# PWM_WIDTH.net
KiCad netlist of a schematic drawn in Altium Designer
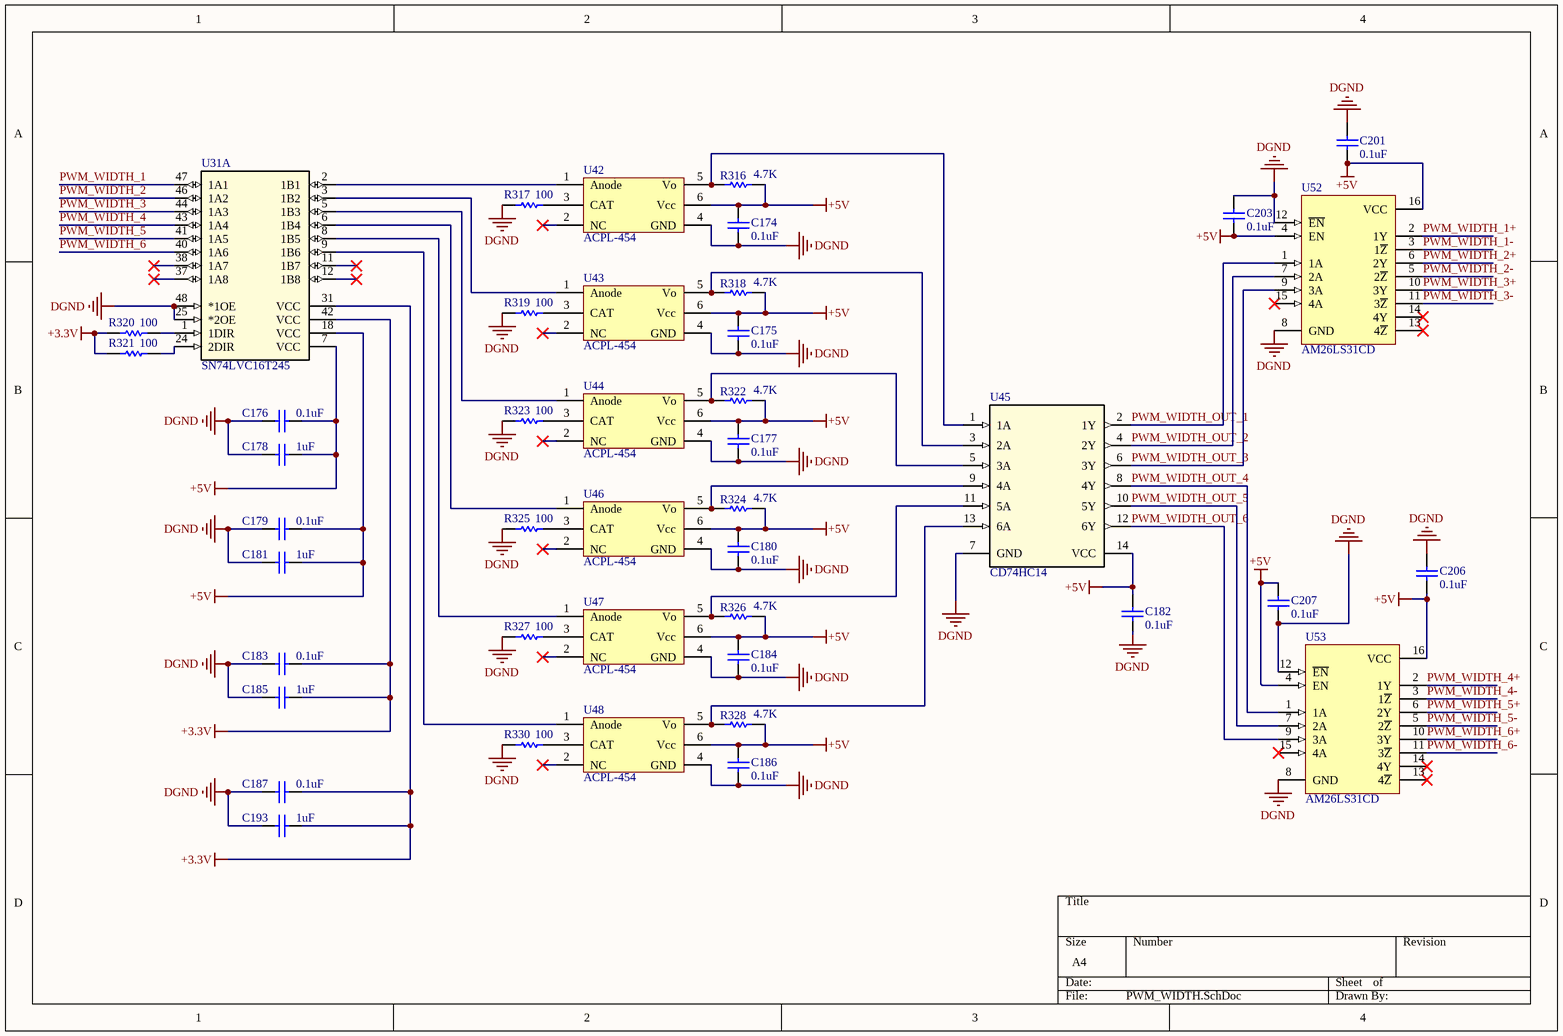
[diagram p0: PWM_WIDTH.SchDoc]

(export (version "E")
  (design (tool "Eeschema 10.0.6"))
  (components
    (comp (ref "C174")
      (value "0.1uF")
      (footprint "1608[0603]")
      (description "Capacitor")
      (fields (field (name "Comment") "Cap") (field (name "PUBLISHER") "Altium Limited"))
      (libsource (lib "Miscellaneous Devices") (part "Cap"))
    )
    (comp (ref "C175")
      (value "0.1uF")
      (footprint "1608[0603]")
      (description "Capacitor")
      (fields (field (name "Comment") "Cap") (field (name "PUBLISHER") "Altium Limited"))
      (libsource (lib "Miscellaneous Devices") (part "Cap"))
    )
    (comp (ref "C176")
      (value "0.1uF")
      (footprint "1608[0603]")
      (description "Capacitor")
      (fields (field (name "Comment") "Cap") (field (name "PUBLISHER") "Altium Limited"))
      (libsource (lib "Miscellaneous Devices") (part "Cap"))
    )
    (comp (ref "C177")
      (value "0.1uF")
      (footprint "1608[0603]")
      (description "Capacitor")
      (fields (field (name "Comment") "Cap") (field (name "PUBLISHER") "Altium Limited"))
      (libsource (lib "Miscellaneous Devices") (part "Cap"))
    )
    (comp (ref "C178")
      (value "1uF")
      (footprint "1608[0603]")
      (description "Capacitor")
      (fields (field (name "Comment") "Cap") (field (name "PUBLISHER") "Altium Limited"))
      (libsource (lib "Miscellaneous Devices") (part "Cap"))
    )
    (comp (ref "C179")
      (value "0.1uF")
      (footprint "1608[0603]")
      (description "Capacitor")
      (fields (field (name "Comment") "Cap") (field (name "PUBLISHER") "Altium Limited"))
      (libsource (lib "Miscellaneous Devices") (part "Cap"))
    )
    (comp (ref "C180")
      (value "0.1uF")
      (footprint "1608[0603]")
      (description "Capacitor")
      (fields (field (name "Comment") "Cap") (field (name "PUBLISHER") "Altium Limited"))
      (libsource (lib "Miscellaneous Devices") (part "Cap"))
    )
    (comp (ref "C181")
      (value "1uF")
      (footprint "1608[0603]")
      (description "Capacitor")
      (fields (field (name "Comment") "Cap") (field (name "PUBLISHER") "Altium Limited"))
      (libsource (lib "Miscellaneous Devices") (part "Cap"))
    )
    (comp (ref "C182")
      (value "0.1uF")
      (footprint "1608[0603]")
      (description "Capacitor")
      (fields (field (name "Comment") "Cap") (field (name "PUBLISHER") "Altium Limited"))
      (libsource (lib "Miscellaneous Devices") (part "Cap"))
    )
    (comp (ref "C183")
      (value "0.1uF")
      (footprint "1608[0603]")
      (description "Capacitor")
      (fields (field (name "Comment") "Cap") (field (name "PUBLISHER") "Altium Limited"))
      (libsource (lib "Miscellaneous Devices") (part "Cap"))
    )
    (comp (ref "C184")
      (value "0.1uF")
      (footprint "1608[0603]")
      (description "Capacitor")
      (fields (field (name "Comment") "Cap") (field (name "PUBLISHER") "Altium Limited"))
      (libsource (lib "Miscellaneous Devices") (part "Cap"))
    )
    (comp (ref "C185")
      (value "1uF")
      (footprint "1608[0603]")
      (description "Capacitor")
      (fields (field (name "Comment") "Cap") (field (name "PUBLISHER") "Altium Limited"))
      (libsource (lib "Miscellaneous Devices") (part "Cap"))
    )
    (comp (ref "C186")
      (value "0.1uF")
      (footprint "1608[0603]")
      (description "Capacitor")
      (fields (field (name "Comment") "Cap") (field (name "PUBLISHER") "Altium Limited"))
      (libsource (lib "Miscellaneous Devices") (part "Cap"))
    )
    (comp (ref "C187")
      (value "0.1uF")
      (footprint "1608[0603]")
      (description "Capacitor")
      (fields (field (name "Comment") "Cap") (field (name "PUBLISHER") "Altium Limited"))
      (libsource (lib "Miscellaneous Devices") (part "Cap"))
    )
    (comp (ref "C193")
      (value "1uF")
      (footprint "1608[0603]")
      (description "Capacitor")
      (fields (field (name "Comment") "Cap") (field (name "PUBLISHER") "Altium Limited"))
      (libsource (lib "Miscellaneous Devices") (part "Cap"))
    )
    (comp (ref "C201")
      (value "0.1uF")
      (footprint "1608[0603]")
      (description "Capacitor")
      (fields (field (name "Comment") "Cap") (field (name "PUBLISHER") "Altium Limited"))
      (libsource (lib "Miscellaneous Devices") (part "Cap"))
    )
    (comp (ref "C203")
      (value "0.1uF")
      (footprint "1608[0603]")
      (description "Capacitor")
      (fields (field (name "Comment") "Cap") (field (name "PUBLISHER") "Altium Limited"))
      (libsource (lib "Miscellaneous Devices") (part "Cap"))
    )
    (comp (ref "C206")
      (value "0.1uF")
      (footprint "1608[0603]")
      (description "Capacitor")
      (fields (field (name "Comment") "Cap") (field (name "PUBLISHER") "Altium Limited"))
      (libsource (lib "Miscellaneous Devices") (part "Cap"))
    )
    (comp (ref "C207")
      (value "0.1uF")
      (footprint "1608[0603]")
      (description "Capacitor")
      (fields (field (name "Comment") "Cap") (field (name "PUBLISHER") "Altium Limited"))
      (libsource (lib "Miscellaneous Devices") (part "Cap"))
    )
    (comp (ref "R316")
      (value "4.7K")
      (footprint "1608[0603]")
      (description "Resistor")
      (fields (field (name "Comment") "Res1") (field (name "PUBLISHER") "Altium Limited"))
      (libsource (lib "Miscellaneous Devices") (part "Res1"))
    )
    (comp (ref "R317")
      (value "100")
      (footprint "1608[0603]")
      (description "Resistor")
      (fields (field (name "Comment") "Res1") (field (name "PUBLISHER") "Altium Limited"))
      (libsource (lib "Miscellaneous Devices") (part "Res1"))
    )
    (comp (ref "R318")
      (value "4.7K")
      (footprint "1608[0603]")
      (description "Resistor")
      (fields (field (name "Comment") "Res1") (field (name "PUBLISHER") "Altium Limited"))
      (libsource (lib "Miscellaneous Devices") (part "Res1"))
    )
    (comp (ref "R319")
      (value "100")
      (footprint "1608[0603]")
      (description "Resistor")
      (fields (field (name "Comment") "Res1") (field (name "PUBLISHER") "Altium Limited"))
      (libsource (lib "Miscellaneous Devices") (part "Res1"))
    )
    (comp (ref "R320")
      (value "100")
      (footprint "1608[0603]")
      (description "Resistor")
      (fields (field (name "Comment") "Res1") (field (name "PUBLISHER") "Altium Limited"))
      (libsource (lib "Miscellaneous Devices") (part "Res1"))
    )
    (comp (ref "R321")
      (value "100")
      (footprint "1608[0603]")
      (description "Resistor")
      (fields (field (name "Comment") "Res1") (field (name "PUBLISHER") "Altium Limited"))
      (libsource (lib "Miscellaneous Devices") (part "Res1"))
    )
    (comp (ref "R322")
      (value "4.7K")
      (footprint "1608[0603]")
      (description "Resistor")
      (fields (field (name "Comment") "Res1") (field (name "PUBLISHER") "Altium Limited"))
      (libsource (lib "Miscellaneous Devices") (part "Res1"))
    )
    (comp (ref "R323")
      (value "100")
      (footprint "1608[0603]")
      (description "Resistor")
      (fields (field (name "Comment") "Res1") (field (name "PUBLISHER") "Altium Limited"))
      (libsource (lib "Miscellaneous Devices") (part "Res1"))
    )
    (comp (ref "R324")
      (value "4.7K")
      (footprint "1608[0603]")
      (description "Resistor")
      (fields (field (name "Comment") "Res1") (field (name "PUBLISHER") "Altium Limited"))
      (libsource (lib "Miscellaneous Devices") (part "Res1"))
    )
    (comp (ref "R325")
      (value "100")
      (footprint "1608[0603]")
      (description "Resistor")
      (fields (field (name "Comment") "Res1") (field (name "PUBLISHER") "Altium Limited"))
      (libsource (lib "Miscellaneous Devices") (part "Res1"))
    )
    (comp (ref "R326")
      (value "4.7K")
      (footprint "1608[0603]")
      (description "Resistor")
      (fields (field (name "Comment") "Res1") (field (name "PUBLISHER") "Altium Limited"))
      (libsource (lib "Miscellaneous Devices") (part "Res1"))
    )
    (comp (ref "R327")
      (value "100")
      (footprint "1608[0603]")
      (description "Resistor")
      (fields (field (name "Comment") "Res1") (field (name "PUBLISHER") "Altium Limited"))
      (libsource (lib "Miscellaneous Devices") (part "Res1"))
    )
    (comp (ref "R328")
      (value "4.7K")
      (footprint "1608[0603]")
      (description "Resistor")
      (fields (field (name "Comment") "Res1") (field (name "PUBLISHER") "Altium Limited"))
      (libsource (lib "Miscellaneous Devices") (part "Res1"))
    )
    (comp (ref "R330")
      (value "100")
      (footprint "1608[0603]")
      (description "Resistor")
      (fields (field (name "Comment") "Res1") (field (name "PUBLISHER") "Altium Limited"))
      (libsource (lib "Miscellaneous Devices") (part "Res1"))
    )
    (comp (ref "U31")
      (value "SN74LVC16T245")
      (footprint "SN74LVC16T245_TSSOP")
      (libsource (lib "DSP_FPGA_Lib") (part "SN74LVC16T245_A"))
    )
    (comp (ref "U42")
      (value "ACPL-454")
      (footprint "ACPL-P454")
      (libsource (lib "DSP_FPGA_Lib") (part "ACPL-454"))
    )
    (comp (ref "U43")
      (value "ACPL-454")
      (footprint "ACPL-P454")
      (libsource (lib "DSP_FPGA_Lib") (part "ACPL-454"))
    )
    (comp (ref "U44")
      (value "ACPL-454")
      (footprint "ACPL-P454")
      (libsource (lib "DSP_FPGA_Lib") (part "ACPL-454"))
    )
    (comp (ref "U45")
      (value "CD74HC14")
      (footprint "CD74HC14_SOIC")
      (fields (field (name "MANUFACTURER") "Texas Instruments"))
      (libsource (lib "DSP_FPGA_Lib") (part "CD74HC14"))
    )
    (comp (ref "U46")
      (value "ACPL-454")
      (footprint "ACPL-P454")
      (libsource (lib "DSP_FPGA_Lib") (part "ACPL-454"))
    )
    (comp (ref "U47")
      (value "ACPL-454")
      (footprint "ACPL-P454")
      (libsource (lib "DSP_FPGA_Lib") (part "ACPL-454"))
    )
    (comp (ref "U48")
      (value "ACPL-454")
      (footprint "ACPL-P454")
      (libsource (lib "DSP_FPGA_Lib") (part "ACPL-454"))
    )
    (comp (ref "U52")
      (value "AM26LS31CD")
      (footprint "D016_N")
      (description "Quadruple Differential Line Driver")
      (fields (field (name "PUBLISHER") "Altium Limited"))
      (libsource (lib "TI Interface Line Driver") (part "AM26LS31CD"))
    )
    (comp (ref "U53")
      (value "AM26LS31CD")
      (footprint "D016_N")
      (description "Quadruple Differential Line Driver")
      (fields (field (name "PUBLISHER") "Altium Limited"))
      (libsource (lib "TI Interface Line Driver") (part "AM26LS31CD"))
    )
  )
  (nets
    (net (code "1") (name "+3.3V") (class "Default")
      (node (ref "C183") (pin "1") (pinfunction "1_1") (pintype "passive"))
      (node (ref "C185") (pin "1") (pinfunction "1_1") (pintype "passive"))
      (node (ref "C187") (pin "1") (pinfunction "1_1") (pintype "passive"))
      (node (ref "C193") (pin "1") (pinfunction "1_1") (pintype "passive"))
      (node (ref "R320") (pin "2") (pinfunction "2_2") (pintype "passive"))
      (node (ref "R321") (pin "2") (pinfunction "2_2") (pintype "passive"))
      (node (ref "U31") (pin "31") (pinfunction "VCC_31") (pintype "power_in"))
      (node (ref "U31") (pin "42") (pinfunction "VCC_42") (pintype "power_in"))
    )
    (net (code "2") (name "+5V") (class "Default")
      (node (ref "C174") (pin "2") (pinfunction "2_2") (pintype "passive"))
      (node (ref "C175") (pin "2") (pinfunction "2_2") (pintype "passive"))
      (node (ref "C176") (pin "1") (pinfunction "1_1") (pintype "passive"))
      (node (ref "C177") (pin "2") (pinfunction "2_2") (pintype "passive"))
      (node (ref "C178") (pin "1") (pinfunction "1_1") (pintype "passive"))
      (node (ref "C179") (pin "1") (pinfunction "1_1") (pintype "passive"))
      (node (ref "C180") (pin "2") (pinfunction "2_2") (pintype "passive"))
      (node (ref "C181") (pin "1") (pinfunction "1_1") (pintype "passive"))
      (node (ref "C182") (pin "2") (pinfunction "2_2") (pintype "passive"))
      (node (ref "C184") (pin "2") (pinfunction "2_2") (pintype "passive"))
      (node (ref "C186") (pin "2") (pinfunction "2_2") (pintype "passive"))
      (node (ref "C201") (pin "2") (pinfunction "2_2") (pintype "passive"))
      (node (ref "C203") (pin "1") (pinfunction "1_1") (pintype "passive"))
      (node (ref "C206") (pin "1") (pinfunction "1_1") (pintype "passive"))
      (node (ref "C207") (pin "2") (pinfunction "2_2") (pintype "passive"))
      (node (ref "R316") (pin "1") (pinfunction "1_1") (pintype "passive"))
      (node (ref "R318") (pin "1") (pinfunction "1_1") (pintype "passive"))
      (node (ref "R322") (pin "1") (pinfunction "1_1") (pintype "passive"))
      (node (ref "R324") (pin "1") (pinfunction "1_1") (pintype "passive"))
      (node (ref "R326") (pin "1") (pinfunction "1_1") (pintype "passive"))
      (node (ref "R328") (pin "1") (pinfunction "1_1") (pintype "passive"))
      (node (ref "U31") (pin "18") (pinfunction "VCC_18") (pintype "power_in"))
      (node (ref "U31") (pin "7") (pinfunction "VCC_7") (pintype "power_in"))
      (node (ref "U42") (pin "6") (pinfunction "Vcc_6") (pintype "passive"))
      (node (ref "U43") (pin "6") (pinfunction "Vcc_6") (pintype "passive"))
      (node (ref "U44") (pin "6") (pinfunction "Vcc_6") (pintype "passive"))
      (node (ref "U45") (pin "14") (pinfunction "VCC_14") (pintype "power_in"))
      (node (ref "U46") (pin "6") (pinfunction "Vcc_6") (pintype "passive"))
      (node (ref "U47") (pin "6") (pinfunction "Vcc_6") (pintype "passive"))
      (node (ref "U48") (pin "6") (pinfunction "Vcc_6") (pintype "passive"))
      (node (ref "U52") (pin "16") (pinfunction "VCC_16") (pintype "power_in"))
      (node (ref "U52") (pin "4") (pinfunction "EN_4") (pintype "input"))
      (node (ref "U53") (pin "16") (pinfunction "VCC_16") (pintype "power_in"))
      (node (ref "U53") (pin "4") (pinfunction "EN_4") (pintype "input"))
    )
    (net (code "3") (name "/PWM_WIDTH_1") (class "Default")
      (node (ref "U31") (pin "47") (pinfunction "1A1_47") (pintype "bidirectional"))
    )
    (net (code "4") (name "/PWM_WIDTH_1+") (class "Default")
      (node (ref "U52") (pin "2") (pinfunction "1Y_2") (pintype "tri_state"))
    )
    (net (code "5") (name "/PWM_WIDTH_1-") (class "Default")
      (node (ref "U52") (pin "3") (pinfunction "1~{Z}_3") (pintype "tri_state"))
    )
    (net (code "6") (name "/PWM_WIDTH_2") (class "Default")
      (node (ref "U31") (pin "46") (pinfunction "1A2_46") (pintype "bidirectional"))
    )
    (net (code "7") (name "/PWM_WIDTH_2+") (class "Default")
      (node (ref "U52") (pin "6") (pinfunction "2Y_6") (pintype "tri_state"))
    )
    (net (code "8") (name "/PWM_WIDTH_2-") (class "Default")
      (node (ref "U52") (pin "5") (pinfunction "2~{Z}_5") (pintype "tri_state"))
    )
    (net (code "9") (name "/PWM_WIDTH_3") (class "Default")
      (node (ref "U31") (pin "44") (pinfunction "1A3_44") (pintype "bidirectional"))
    )
    (net (code "10") (name "/PWM_WIDTH_3+") (class "Default")
      (node (ref "U52") (pin "10") (pinfunction "3Y_10") (pintype "tri_state"))
    )
    (net (code "11") (name "/PWM_WIDTH_3-") (class "Default")
      (node (ref "U52") (pin "11") (pinfunction "3~{Z}_11") (pintype "tri_state"))
    )
    (net (code "12") (name "/PWM_WIDTH_4") (class "Default")
      (node (ref "U31") (pin "43") (pinfunction "1A4_43") (pintype "bidirectional"))
    )
    (net (code "13") (name "/PWM_WIDTH_4+") (class "Default")
      (node (ref "U53") (pin "2") (pinfunction "1Y_2") (pintype "tri_state"))
    )
    (net (code "14") (name "/PWM_WIDTH_4-") (class "Default")
      (node (ref "U53") (pin "3") (pinfunction "1~{Z}_3") (pintype "tri_state"))
    )
    (net (code "15") (name "/PWM_WIDTH_5") (class "Default")
      (node (ref "U31") (pin "41") (pinfunction "1A5_41") (pintype "bidirectional"))
    )
    (net (code "16") (name "/PWM_WIDTH_5+") (class "Default")
      (node (ref "U53") (pin "6") (pinfunction "2Y_6") (pintype "tri_state"))
    )
    (net (code "17") (name "/PWM_WIDTH_5-") (class "Default")
      (node (ref "U53") (pin "5") (pinfunction "2~{Z}_5") (pintype "tri_state"))
    )
    (net (code "18") (name "/PWM_WIDTH_6") (class "Default")
      (node (ref "U31") (pin "40") (pinfunction "1A6_40") (pintype "bidirectional"))
    )
    (net (code "19") (name "/PWM_WIDTH_6+") (class "Default")
      (node (ref "U53") (pin "10") (pinfunction "3Y_10") (pintype "tri_state"))
    )
    (net (code "20") (name "/PWM_WIDTH_6-") (class "Default")
      (node (ref "U53") (pin "11") (pinfunction "3~{Z}_11") (pintype "tri_state"))
    )
    (net (code "21") (name "/PWM_WIDTH_OUT_1") (class "Default")
      (node (ref "U45") (pin "2") (pinfunction "1Y_2") (pintype "output"))
      (node (ref "U52") (pin "1") (pinfunction "1A_1") (pintype "input"))
    )
    (net (code "22") (name "/PWM_WIDTH_OUT_2") (class "Default")
      (node (ref "U45") (pin "4") (pinfunction "2Y_4") (pintype "output"))
      (node (ref "U52") (pin "7") (pinfunction "2A_7") (pintype "input"))
    )
    (net (code "23") (name "/PWM_WIDTH_OUT_3") (class "Default")
      (node (ref "U45") (pin "6") (pinfunction "3Y_6") (pintype "output"))
      (node (ref "U52") (pin "9") (pinfunction "3A_9") (pintype "input"))
    )
    (net (code "24") (name "/PWM_WIDTH_OUT_4") (class "Default")
      (node (ref "U45") (pin "8") (pinfunction "4Y_8") (pintype "output"))
      (node (ref "U53") (pin "1") (pinfunction "1A_1") (pintype "input"))
    )
    (net (code "25") (name "/PWM_WIDTH_OUT_5") (class "Default")
      (node (ref "U45") (pin "10") (pinfunction "5Y_10") (pintype "output"))
      (node (ref "U53") (pin "7") (pinfunction "2A_7") (pintype "input"))
    )
    (net (code "26") (name "/PWM_WIDTH_OUT_6") (class "Default")
      (node (ref "U45") (pin "12") (pinfunction "6Y_12") (pintype "output"))
      (node (ref "U53") (pin "9") (pinfunction "3A_9") (pintype "input"))
    )
    (net (code "27") (name "DGND") (class "Default")
      (node (ref "C174") (pin "1") (pinfunction "1_1") (pintype "passive"))
      (node (ref "C175") (pin "1") (pinfunction "1_1") (pintype "passive"))
      (node (ref "C176") (pin "2") (pinfunction "2_2") (pintype "passive"))
      (node (ref "C177") (pin "1") (pinfunction "1_1") (pintype "passive"))
      (node (ref "C178") (pin "2") (pinfunction "2_2") (pintype "passive"))
      (node (ref "C179") (pin "2") (pinfunction "2_2") (pintype "passive"))
      (node (ref "C180") (pin "1") (pinfunction "1_1") (pintype "passive"))
      (node (ref "C181") (pin "2") (pinfunction "2_2") (pintype "passive"))
      (node (ref "C182") (pin "1") (pinfunction "1_1") (pintype "passive"))
      (node (ref "C183") (pin "2") (pinfunction "2_2") (pintype "passive"))
      (node (ref "C184") (pin "1") (pinfunction "1_1") (pintype "passive"))
      (node (ref "C185") (pin "2") (pinfunction "2_2") (pintype "passive"))
      (node (ref "C186") (pin "1") (pinfunction "1_1") (pintype "passive"))
      (node (ref "C187") (pin "2") (pinfunction "2_2") (pintype "passive"))
      (node (ref "C193") (pin "2") (pinfunction "2_2") (pintype "passive"))
      (node (ref "C201") (pin "1") (pinfunction "1_1") (pintype "passive"))
      (node (ref "C203") (pin "2") (pinfunction "2_2") (pintype "passive"))
      (node (ref "C206") (pin "2") (pinfunction "2_2") (pintype "passive"))
      (node (ref "C207") (pin "1") (pinfunction "1_1") (pintype "passive"))
      (node (ref "R317") (pin "2") (pinfunction "2_2") (pintype "passive"))
      (node (ref "R319") (pin "2") (pinfunction "2_2") (pintype "passive"))
      (node (ref "R323") (pin "2") (pinfunction "2_2") (pintype "passive"))
      (node (ref "R325") (pin "2") (pinfunction "2_2") (pintype "passive"))
      (node (ref "R327") (pin "2") (pinfunction "2_2") (pintype "passive"))
      (node (ref "R330") (pin "2") (pinfunction "2_2") (pintype "passive"))
      (node (ref "U31") (pin "25") (pinfunction "*2OE_25") (pintype "input"))
      (node (ref "U31") (pin "48") (pinfunction "*1OE_48") (pintype "input"))
      (node (ref "U42") (pin "4") (pinfunction "GND_4") (pintype "passive"))
      (node (ref "U43") (pin "4") (pinfunction "GND_4") (pintype "passive"))
      (node (ref "U44") (pin "4") (pinfunction "GND_4") (pintype "passive"))
      (node (ref "U45") (pin "7") (pinfunction "GND_7") (pintype "power_in"))
      (node (ref "U46") (pin "4") (pinfunction "GND_4") (pintype "passive"))
      (node (ref "U47") (pin "4") (pinfunction "GND_4") (pintype "passive"))
      (node (ref "U48") (pin "4") (pinfunction "GND_4") (pintype "passive"))
      (node (ref "U52") (pin "12") (pinfunction "~{EN}_12") (pintype "input"))
      (node (ref "U52") (pin "8") (pinfunction "GND_8") (pintype "power_in"))
      (node (ref "U53") (pin "12") (pinfunction "~{EN}_12") (pintype "input"))
      (node (ref "U53") (pin "8") (pinfunction "GND_8") (pintype "power_in"))
    )
    (net (code "28") (name "Net-(U31A-1B1)") (class "Default")
      (node (ref "U31") (pin "2") (pinfunction "1B1_2") (pintype "bidirectional"))
      (node (ref "U42") (pin "1") (pinfunction "Anode_1") (pintype "passive"))
    )
    (net (code "29") (name "Net-(U31A-1B2)") (class "Default")
      (node (ref "U31") (pin "3") (pinfunction "1B2_3") (pintype "bidirectional"))
      (node (ref "U43") (pin "1") (pinfunction "Anode_1") (pintype "passive"))
    )
    (net (code "30") (name "Net-(U31A-1B3)") (class "Default")
      (node (ref "U31") (pin "5") (pinfunction "1B3_5") (pintype "bidirectional"))
      (node (ref "U44") (pin "1") (pinfunction "Anode_1") (pintype "passive"))
    )
    (net (code "31") (name "Net-(U31A-1B4)") (class "Default")
      (node (ref "U31") (pin "6") (pinfunction "1B4_6") (pintype "bidirectional"))
      (node (ref "U46") (pin "1") (pinfunction "Anode_1") (pintype "passive"))
    )
    (net (code "32") (name "Net-(U31A-1B5)") (class "Default")
      (node (ref "U31") (pin "8") (pinfunction "1B5_8") (pintype "bidirectional"))
      (node (ref "U47") (pin "1") (pinfunction "Anode_1") (pintype "passive"))
    )
    (net (code "33") (name "Net-(U31A-1B6)") (class "Default")
      (node (ref "U31") (pin "9") (pinfunction "1B6_9") (pintype "bidirectional"))
      (node (ref "U48") (pin "1") (pinfunction "Anode_1") (pintype "passive"))
    )
    (net (code "34") (name "Net-(U31A-1DIR)") (class "Default")
      (node (ref "R320") (pin "1") (pinfunction "1_1") (pintype "passive"))
      (node (ref "U31") (pin "1") (pinfunction "1DIR_1") (pintype "input"))
    )
    (net (code "35") (name "Net-(U31A-2DIR)") (class "Default")
      (node (ref "R321") (pin "1") (pinfunction "1_1") (pintype "passive"))
      (node (ref "U31") (pin "24") (pinfunction "2DIR_24") (pintype "input"))
    )
    (net (code "36") (name "Net-(U42-CAT)") (class "Default")
      (node (ref "R317") (pin "1") (pinfunction "1_1") (pintype "passive"))
      (node (ref "U42") (pin "3") (pinfunction "CAT_3") (pintype "passive"))
    )
    (net (code "37") (name "Net-(U42-Vo)") (class "Default")
      (node (ref "R316") (pin "2") (pinfunction "2_2") (pintype "passive"))
      (node (ref "U42") (pin "5") (pinfunction "Vo_5") (pintype "passive"))
      (node (ref "U45") (pin "1") (pinfunction "1A_1") (pintype "input"))
    )
    (net (code "38") (name "Net-(U43-CAT)") (class "Default")
      (node (ref "R319") (pin "1") (pinfunction "1_1") (pintype "passive"))
      (node (ref "U43") (pin "3") (pinfunction "CAT_3") (pintype "passive"))
    )
    (net (code "39") (name "Net-(U43-Vo)") (class "Default")
      (node (ref "R318") (pin "2") (pinfunction "2_2") (pintype "passive"))
      (node (ref "U43") (pin "5") (pinfunction "Vo_5") (pintype "passive"))
      (node (ref "U45") (pin "3") (pinfunction "2A_3") (pintype "input"))
    )
    (net (code "40") (name "Net-(U44-CAT)") (class "Default")
      (node (ref "R323") (pin "1") (pinfunction "1_1") (pintype "passive"))
      (node (ref "U44") (pin "3") (pinfunction "CAT_3") (pintype "passive"))
    )
    (net (code "41") (name "Net-(U44-Vo)") (class "Default")
      (node (ref "R322") (pin "2") (pinfunction "2_2") (pintype "passive"))
      (node (ref "U44") (pin "5") (pinfunction "Vo_5") (pintype "passive"))
      (node (ref "U45") (pin "5") (pinfunction "3A_5") (pintype "input"))
    )
    (net (code "42") (name "Net-(U45-4A)") (class "Default")
      (node (ref "R324") (pin "2") (pinfunction "2_2") (pintype "passive"))
      (node (ref "U45") (pin "9") (pinfunction "4A_9") (pintype "input"))
      (node (ref "U46") (pin "5") (pinfunction "Vo_5") (pintype "passive"))
    )
    (net (code "43") (name "Net-(U45-5A)") (class "Default")
      (node (ref "R326") (pin "2") (pinfunction "2_2") (pintype "passive"))
      (node (ref "U45") (pin "11") (pinfunction "5A_11") (pintype "input"))
      (node (ref "U47") (pin "5") (pinfunction "Vo_5") (pintype "passive"))
    )
    (net (code "44") (name "Net-(U45-6A)") (class "Default")
      (node (ref "R328") (pin "2") (pinfunction "2_2") (pintype "passive"))
      (node (ref "U45") (pin "13") (pinfunction "6A_13") (pintype "input"))
      (node (ref "U48") (pin "5") (pinfunction "Vo_5") (pintype "passive"))
    )
    (net (code "45") (name "Net-(U46-CAT)") (class "Default")
      (node (ref "R325") (pin "1") (pinfunction "1_1") (pintype "passive"))
      (node (ref "U46") (pin "3") (pinfunction "CAT_3") (pintype "passive"))
    )
    (net (code "46") (name "Net-(U47-CAT)") (class "Default")
      (node (ref "R327") (pin "1") (pinfunction "1_1") (pintype "passive"))
      (node (ref "U47") (pin "3") (pinfunction "CAT_3") (pintype "passive"))
    )
    (net (code "47") (name "Net-(U48-CAT)") (class "Default")
      (node (ref "R330") (pin "1") (pinfunction "1_1") (pintype "passive"))
      (node (ref "U48") (pin "3") (pinfunction "CAT_3") (pintype "passive"))
    )
    (net (code "48") (name "unconnected-(U31A-1A7-Pad38)") (class "Default")
      (node (ref "U31") (pin "38") (pinfunction "1A7_38") (pintype "bidirectional+no_connect"))
    )
    (net (code "49") (name "unconnected-(U31A-1A8-Pad37)") (class "Default")
      (node (ref "U31") (pin "37") (pinfunction "1A8_37") (pintype "bidirectional+no_connect"))
    )
    (net (code "50") (name "unconnected-(U31A-1B7-Pad11)") (class "Default")
      (node (ref "U31") (pin "11") (pinfunction "1B7_11") (pintype "bidirectional+no_connect"))
    )
    (net (code "51") (name "unconnected-(U31A-1B8-Pad12)") (class "Default")
      (node (ref "U31") (pin "12") (pinfunction "1B8_12") (pintype "bidirectional+no_connect"))
    )
    (net (code "52") (name "unconnected-(U42-NC-Pad2)") (class "Default")
      (node (ref "U42") (pin "2") (pinfunction "NC_2") (pintype "passive+no_connect"))
    )
    (net (code "53") (name "unconnected-(U43-NC-Pad2)") (class "Default")
      (node (ref "U43") (pin "2") (pinfunction "NC_2") (pintype "passive+no_connect"))
    )
    (net (code "54") (name "unconnected-(U44-NC-Pad2)") (class "Default")
      (node (ref "U44") (pin "2") (pinfunction "NC_2") (pintype "passive+no_connect"))
    )
    (net (code "55") (name "unconnected-(U46-NC-Pad2)") (class "Default")
      (node (ref "U46") (pin "2") (pinfunction "NC_2") (pintype "passive+no_connect"))
    )
    (net (code "56") (name "unconnected-(U47-NC-Pad2)") (class "Default")
      (node (ref "U47") (pin "2") (pinfunction "NC_2") (pintype "passive+no_connect"))
    )
    (net (code "57") (name "unconnected-(U48-NC-Pad2)") (class "Default")
      (node (ref "U48") (pin "2") (pinfunction "NC_2") (pintype "passive+no_connect"))
    )
    (net (code "58") (name "unconnected-(U52-4A-Pad15)") (class "Default")
      (node (ref "U52") (pin "15") (pinfunction "4A_15") (pintype "input+no_connect"))
    )
    (net (code "59") (name "unconnected-(U52-4Y-Pad14)") (class "Default")
      (node (ref "U52") (pin "14") (pinfunction "4Y_14") (pintype "tri_state+no_connect"))
    )
    (net (code "60") (name "unconnected-(U52-4~{Z}-Pad13)") (class "Default")
      (node (ref "U52") (pin "13") (pinfunction "4~{Z}_13") (pintype "tri_state+no_connect"))
    )
    (net (code "61") (name "unconnected-(U53-4A-Pad15)") (class "Default")
      (node (ref "U53") (pin "15") (pinfunction "4A_15") (pintype "input+no_connect"))
    )
    (net (code "62") (name "unconnected-(U53-4Y-Pad14)") (class "Default")
      (node (ref "U53") (pin "14") (pinfunction "4Y_14") (pintype "tri_state+no_connect"))
    )
    (net (code "63") (name "unconnected-(U53-4~{Z}-Pad13)") (class "Default")
      (node (ref "U53") (pin "13") (pinfunction "4~{Z}_13") (pintype "tri_state+no_connect"))
    )
  )
)
